# IRsensor_Relayx1_Controller.net
KiCad netlist of a schematic drawn in Altium Designer
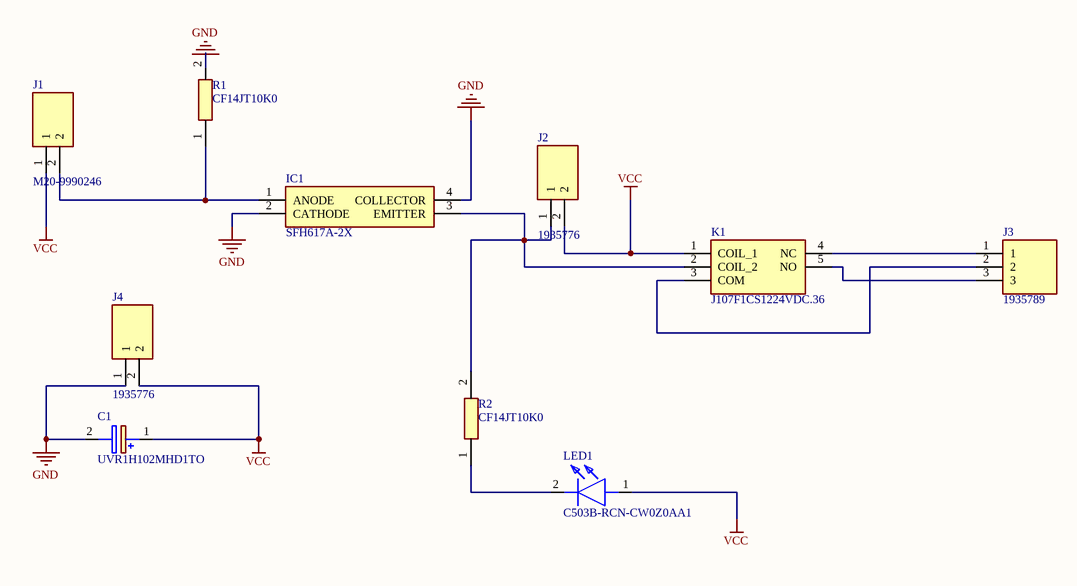
[diagram p0: IRsensor_Relayx1_Controller.SchDoc]

(export (version "E")
  (design (tool "Eeschema 10.0.6"))
  (components
    (comp (ref "C1")
      (value "UVR1H102MHD1TO")
      (footprint "SamacSys:CAPPRD500W60D1275H2700")
      (description "Capacitor Polarised")
      (fields (field (name "MOUSER PART NUMBER") "647-UVR1H102MHD1T0"))
      (libsource (lib "*") (part "UVR1H102MHD1TO"))
    )
    (comp (ref "IC1")
      (value "SFH617A-2X")
      (footprint "SamacSys:DIP762W50P254L458H400Q4N")
      (description "Integrated Circuit")
      (libsource (lib "*") (part "SFH617A-2X"))
    )
    (comp (ref "J1")
      (value "M20-9990246")
      (footprint "SamacSys:HDRV2W66P0X254_1X2_508X254X874P")
      (description "Connector")
      (fields (field (name "MOUSER PART NUMBER") "855-M20-9990246"))
      (libsource (lib "*") (part "M20-9990246"))
    )
    (comp (ref "J2")
      (value "1935776")
      (footprint "SamacSys:1935776")
      (description "Connector")
      (fields (field (name "MOUSER PART NUMBER") "651-1935776"))
      (libsource (lib "*") (part "1935776"))
    )
    (comp (ref "J3")
      (value "1935789")
      (footprint "SamacSys:1935789")
      (description "Connector")
      (fields (field (name "MOUSER PART NUMBER") "651-1935789"))
      (libsource (lib "*") (part "1935789"))
    )
    (comp (ref "J4")
      (value "1935776")
      (footprint "SamacSys:1935776")
      (description "Connector")
      (fields (field (name "MOUSER PART NUMBER") "651-1935776"))
      (libsource (lib "*") (part "1935776"))
    )
    (comp (ref "K1")
      (value "J107F1CS1224VDC.36")
      (footprint "SamacSys:J107F1CS1224VDC36")
      (description "Relay or Contactor")
      (libsource (lib "*") (part "J107F1CS1224VDC.36"))
    )
    (comp (ref "LED1")
      (value "C503B-RCN-CW0Z0AA1")
      (footprint "SamacSys:C503BRCNCW0Z0AA1")
      (description "LED")
      (fields (field (name "MOUSER PART NUMBER") "941-C503BRCNCW0Z0AA1"))
      (libsource (lib "*") (part "C503B-RCN-CW0Z0AA1"))
    )
    (comp (ref "R1")
      (value "CF14JT10K0")
      (footprint "SamacSys:RESAD1520W63L600D230")
      (description "Resistor")
      (libsource (lib "*") (part "CF14JT10K0"))
    )
    (comp (ref "R2")
      (value "CF14JT10K0")
      (footprint "SamacSys:RESAD1520W63L600D230")
      (description "Resistor")
      (libsource (lib "*") (part "CF14JT10K0"))
    )
  )
  (nets
    (net (code "1") (name "GND") (class "Default")
      (node (ref "C1") (pin "2") (pinfunction "-_2") (pintype "passive"))
      (node (ref "IC1") (pin "2") (pinfunction "CATHODE_2") (pintype "passive"))
      (node (ref "IC1") (pin "4") (pinfunction "COLLECTOR_4") (pintype "passive"))
      (node (ref "J4") (pin "1") (pinfunction "1_1") (pintype "passive"))
      (node (ref "R1") (pin "2") (pinfunction "2_2") (pintype "passive"))
    )
    (net (code "2") (name "Net-(IC1-ANODE)") (class "Default")
      (node (ref "IC1") (pin "1") (pinfunction "ANODE_1") (pintype "passive"))
      (node (ref "J1") (pin "2") (pinfunction "2_2") (pintype "passive"))
      (node (ref "R1") (pin "1") (pinfunction "1_1") (pintype "passive"))
    )
    (net (code "3") (name "Net-(IC1-EMITTER)") (class "Default")
      (node (ref "IC1") (pin "3") (pinfunction "EMITTER_3") (pintype "passive"))
      (node (ref "J2") (pin "1") (pinfunction "1_1") (pintype "passive"))
      (node (ref "K1") (pin "2") (pinfunction "COIL_2_2") (pintype "passive"))
      (node (ref "R2") (pin "2") (pinfunction "2_2") (pintype "passive"))
    )
    (net (code "4") (name "Net-(K1-COM)") (class "Default")
      (node (ref "J3") (pin "2") (pinfunction "2_2") (pintype "passive"))
      (node (ref "K1") (pin "3") (pinfunction "COM_3") (pintype "passive"))
    )
    (net (code "5") (name "Net-(K1-NC)") (class "Default")
      (node (ref "J3") (pin "1") (pinfunction "1_1") (pintype "passive"))
      (node (ref "K1") (pin "4") (pinfunction "NC_4") (pintype "passive"))
    )
    (net (code "6") (name "Net-(K1-NO)") (class "Default")
      (node (ref "J3") (pin "3") (pinfunction "3_3") (pintype "passive"))
      (node (ref "K1") (pin "5") (pinfunction "NO_5") (pintype "passive"))
    )
    (net (code "7") (name "Net-(LED1-K)") (class "Default")
      (node (ref "LED1") (pin "2") (pinfunction "K_2") (pintype "passive"))
      (node (ref "R2") (pin "1") (pinfunction "1_1") (pintype "passive"))
    )
    (net (code "8") (name "VCC") (class "Default")
      (node (ref "C1") (pin "1") (pinfunction "+_1") (pintype "passive"))
      (node (ref "J1") (pin "1") (pinfunction "1_1") (pintype "passive"))
      (node (ref "J2") (pin "2") (pinfunction "2_2") (pintype "passive"))
      (node (ref "J4") (pin "2") (pinfunction "2_2") (pintype "passive"))
      (node (ref "K1") (pin "1") (pinfunction "COIL_1_1") (pintype "passive"))
      (node (ref "LED1") (pin "1") (pinfunction "A_1") (pintype "passive"))
    )
  )
)
